# DVD.net
KiCad netlist of a schematic drawn in EAGLE
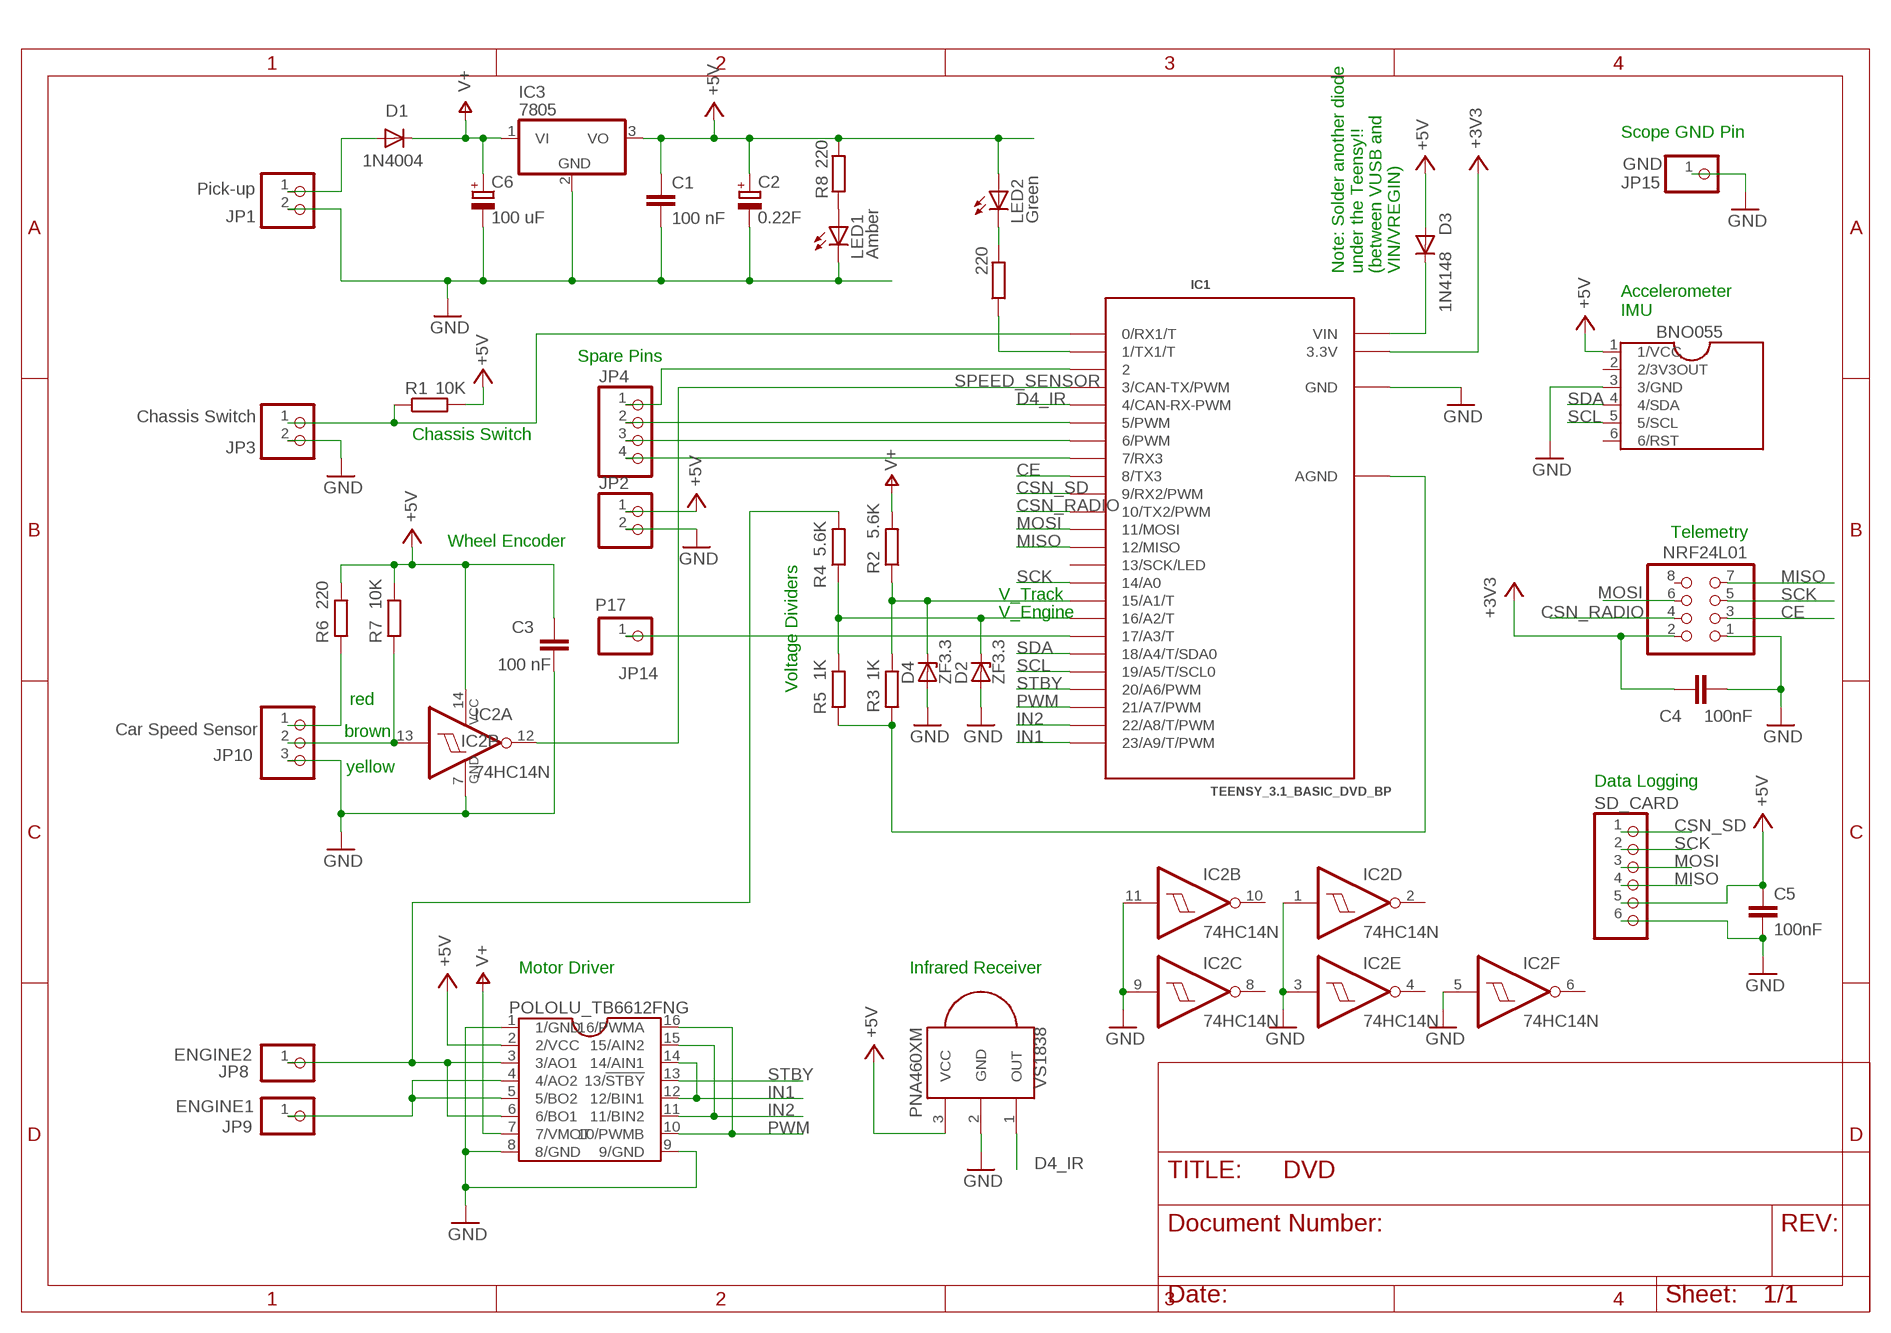
[diagram p0: schematic, sheet 1]

(export (version "E")
  (design (tool "Eeschema 10.0.6"))
  (components
    (comp (ref "BNO055")
      (value "BNO055_LIGHT")
      (footprint "eagle-import:DIL12-6-0")
      (libsource (lib "eagle-import") (part "BNO055_LIGHT"))
    )
    (comp (ref "C1")
      (value "100 nF")
      (footprint "eagle-import:C025-025X050")
      (libsource (lib "eagle-import") (part "resistor_C-EU025-025X050"))
    )
    (comp (ref "C2")
      (value "0.22F")
      (footprint "eagle-import:P128-50")
      (libsource (lib "eagle-import") (part "resistor_CPOL-EUP128-50"))
    )
    (comp (ref "C3")
      (value "100 nF")
      (footprint "eagle-import:C025-025X050")
      (libsource (lib "eagle-import") (part "resistor_C-EU025-025X050"))
    )
    (comp (ref "C4")
      (value "100nF")
      (footprint "eagle-import:C025-025X050")
      (libsource (lib "eagle-import") (part "resistor_C-EU025-025X050"))
    )
    (comp (ref "C5")
      (value "100nF")
      (footprint "eagle-import:C025-024X044")
      (libsource (lib "eagle-import") (part "C-EU025-024X044"))
    )
    (comp (ref "C6")
      (value "100 uF")
      (footprint "eagle-import:E2,5-6")
      (libsource (lib "eagle-import") (part "CPOL-EUE2.5-6"))
    )
    (comp (ref "D1")
      (value "1N4004")
      (footprint "eagle-import:DO41-10")
      (libsource (lib "eagle-import") (part "1N4004"))
    )
    (comp (ref "D2")
      (value "ZF3.3")
      (footprint "eagle-import:ZDIO-7.5")
      (libsource (lib "eagle-import") (part "ZENER-DIODEZD-7.5"))
    )
    (comp (ref "D3")
      (value "1N4148")
      (footprint "eagle-import:DO41-10")
      (libsource (lib "eagle-import") (part "1N4004"))
    )
    (comp (ref "D4")
      (value "ZF3.3")
      (footprint "eagle-import:ZDIO-7.5")
      (libsource (lib "eagle-import") (part "ZENER-DIODEZD-7.5"))
    )
    (comp (ref "IC1")
      (value "TEENSY_3.1_BASIC_DVD_BP")
      (footprint "eagle-import:TEENSY_3.1_BASIC_DVD_BIGPADS")
      (libsource (lib "eagle-import") (part "TEENSY_3.1_BASIC_DVD_BP"))
    )
    (comp (ref "IC2")
      (value "74HC14N")
      (footprint "eagle-import:DIL14")
      (libsource (lib "eagle-import") (part "7414NHC"))
    )
    (comp (ref "IC3")
      (value "7805")
      (footprint "eagle-import:TO220V")
      (libsource (lib "eagle-import") (part "78TV6"))
    )
    (comp (ref "IC4")
      (value "POLOLU_TB6612FNG")
      (footprint "eagle-import:DIL16WIDE")
      (libsource (lib "eagle-import") (part "POLOLU_TB6612FNG"))
    )
    (comp (ref "JP1")
      (value "Pick-up")
      (footprint "eagle-import:1X02")
      (libsource (lib "eagle-import") (part "PINHD-1X2"))
    )
    (comp (ref "JP2")
      (value "PINHD-1X2")
      (footprint "eagle-import:1X02")
      (libsource (lib "eagle-import") (part "PINHD-1X2"))
    )
    (comp (ref "JP3")
      (value "Chassis Switch")
      (footprint "eagle-import:1X02")
      (libsource (lib "eagle-import") (part "PINHD-1X2"))
    )
    (comp (ref "JP4")
      (value "PINHD-1X4")
      (footprint "eagle-import:1X04")
      (libsource (lib "eagle-import") (part "PINHD-1X4"))
    )
    (comp (ref "JP8")
      (value "ENGINE2")
      (footprint "eagle-import:1X01")
      (libsource (lib "eagle-import") (part "PINHD-1X1"))
    )
    (comp (ref "JP9")
      (value "ENGINE1")
      (footprint "eagle-import:1X01")
      (libsource (lib "eagle-import") (part "PINHD-1X1"))
    )
    (comp (ref "JP10")
      (value "Car Speed Sensor")
      (footprint "eagle-import:1X03")
      (libsource (lib "eagle-import") (part "PINHD-1X3"))
    )
    (comp (ref "JP14")
      (value "P17")
      (footprint "eagle-import:1X01")
      (libsource (lib "eagle-import") (part "PINHD-1X1"))
    )
    (comp (ref "JP15")
      (value "GND")
      (footprint "eagle-import:1X01")
      (libsource (lib "eagle-import") (part "PINHD-1X1"))
    )
    (comp (ref "LED1")
      (value "Amber")
      (footprint "eagle-import:LED3MM")
      (libsource (lib "eagle-import") (part "LED3MM"))
    )
    (comp (ref "LED2")
      (value "Green")
      (footprint "eagle-import:LED3MM")
      (libsource (lib "eagle-import") (part "LED3MM"))
    )
    (comp (ref "NRF24L01")
      (value "PINHD-2X4")
      (footprint "eagle-import:2X04")
      (libsource (lib "eagle-import") (part "PINHD-2X4"))
    )
    (comp (ref "R1")
      (value "10K")
      (footprint "eagle-import:0207_10")
      (libsource (lib "eagle-import") (part "R-EU_0207/10"))
    )
    (comp (ref "R2")
      (value "5.6K")
      (footprint "eagle-import:0207_10")
      (libsource (lib "eagle-import") (part "R-EU_0207/10"))
    )
    (comp (ref "R3")
      (value "1K")
      (footprint "eagle-import:0207_10")
      (libsource (lib "eagle-import") (part "R-EU_0207/10"))
    )
    (comp (ref "R4")
      (value "5.6K")
      (footprint "eagle-import:0207_10")
      (libsource (lib "eagle-import") (part "R-EU_0207/10"))
    )
    (comp (ref "R5")
      (value "1K")
      (footprint "eagle-import:0207_10")
      (libsource (lib "eagle-import") (part "R-EU_0207/10"))
    )
    (comp (ref "R6")
      (value "220")
      (footprint "eagle-import:0207_10")
      (libsource (lib "eagle-import") (part "R-EU_0207/10"))
    )
    (comp (ref "R7")
      (value "10K")
      (footprint "eagle-import:0207_10")
      (libsource (lib "eagle-import") (part "R-EU_0207/10"))
    )
    (comp (ref "R8")
      (value "220")
      (footprint "eagle-import:0207_10")
      (libsource (lib "eagle-import") (part "R-EU_0207/10"))
    )
    (comp (ref "R9")
      (value "220")
      (footprint "eagle-import:0207_10")
      (libsource (lib "eagle-import") (part "R-EU_0207/10"))
    )
    (comp (ref "SD_CARD")
      (value "PINHD-1X6")
      (footprint "eagle-import:1X06")
      (libsource (lib "eagle-import") (part "PINHD-1X6"))
    )
    (comp (ref "VS1838")
      (value "PNA460XM")
      (footprint "eagle-import:PNA460XM")
      (libsource (lib "eagle-import") (part "PNA460XM"))
    )
  )
  (nets
    (net (code "1") (name "+3V3") (class "Default")
      (node (ref "C4") (pin "1") (pinfunction "1_1") (pintype "passive"))
      (node (ref "IC1") (pin "3.3V") (pinfunction "3.3V_3.3V") (pintype "power_in"))
      (node (ref "NRF24L01") (pin "2") (pinfunction "2_2") (pintype "passive"))
    )
    (net (code "2") (name "+5V") (class "Default")
      (node (ref "BNO055") (pin "1") (pinfunction "1/VCC_1") (pintype "power_in"))
      (node (ref "C1") (pin "1") (pinfunction "1_1") (pintype "passive"))
      (node (ref "C2") (pin "+") (pinfunction "+_+") (pintype "passive"))
      (node (ref "C3") (pin "1") (pinfunction "1_1") (pintype "passive"))
      (node (ref "C5") (pin "1") (pinfunction "1_1") (pintype "passive"))
      (node (ref "D3") (pin "A") (pinfunction "A_A") (pintype "passive"))
      (node (ref "IC2") (pin "14") (pinfunction "VCC_14") (pintype "power_in"))
      (node (ref "IC3") (pin "3") (pinfunction "VO_3") (pintype "passive"))
      (node (ref "IC4") (pin "2") (pinfunction "2/VCC_2") (pintype "power_in"))
      (node (ref "JP2") (pin "1") (pinfunction "1_1") (pintype "passive"))
      (node (ref "LED2") (pin "A") (pinfunction "A_A") (pintype "passive"))
      (node (ref "R1") (pin "2") (pinfunction "2_2") (pintype "passive"))
      (node (ref "R6") (pin "2") (pinfunction "2_2") (pintype "passive"))
      (node (ref "R7") (pin "2") (pinfunction "2_2") (pintype "passive"))
      (node (ref "R8") (pin "2") (pinfunction "2_2") (pintype "passive"))
      (node (ref "SD_CARD") (pin "5") (pinfunction "5_5") (pintype "passive"))
      (node (ref "VS1838") (pin "3") (pinfunction "VCC_3") (pintype "power_in"))
    )
    (net (code "3") (name "/2{slash}3V3OUT") (class "Default")
      (node (ref "BNO055") (pin "2") (pinfunction "2/3V3OUT_2") (pintype "power_in"))
    )
    (net (code "4") (name "/CE") (class "Default")
      (node (ref "IC1") (pin "8") (pinfunction "8/TX3_8") (pintype "bidirectional"))
      (node (ref "NRF24L01") (pin "3") (pinfunction "3_3") (pintype "passive"))
    )
    (net (code "5") (name "/CSN_RADIO") (class "Default")
      (node (ref "IC1") (pin "10") (pinfunction "10/TX2/PWM_10") (pintype "bidirectional"))
      (node (ref "NRF24L01") (pin "4") (pinfunction "4_4") (pintype "passive"))
    )
    (net (code "6") (name "/CSN_SD") (class "Default")
      (node (ref "IC1") (pin "9") (pinfunction "9/RX2/PWM_9") (pintype "bidirectional"))
      (node (ref "SD_CARD") (pin "1") (pinfunction "1_1") (pintype "passive"))
    )
    (net (code "7") (name "/D4_IR") (class "Default")
      (node (ref "IC1") (pin "4") (pinfunction "4/CAN-RX-PWM_4") (pintype "bidirectional"))
      (node (ref "VS1838") (pin "1") (pinfunction "OUT_1") (pintype "output"))
    )
    (net (code "8") (name "/IN1") (class "Default")
      (node (ref "IC1") (pin "23/A9") (pinfunction "23/A9/T/PWM_23/A9") (pintype "bidirectional"))
      (node (ref "IC4") (pin "12") (pinfunction "12/BIN1_12") (pintype "bidirectional"))
      (node (ref "IC4") (pin "14") (pinfunction "14/AIN1_14") (pintype "bidirectional"))
    )
    (net (code "9") (name "/IN2") (class "Default")
      (node (ref "IC1") (pin "22/A8") (pinfunction "22/A8/T/PWM_22/A8") (pintype "bidirectional"))
      (node (ref "IC4") (pin "11") (pinfunction "11/BIN2_11") (pintype "bidirectional"))
      (node (ref "IC4") (pin "15") (pinfunction "15/AIN2_15") (pintype "bidirectional"))
    )
    (net (code "10") (name "/MISO") (class "Default")
      (node (ref "IC1") (pin "12") (pinfunction "12/MISO_12") (pintype "bidirectional"))
      (node (ref "NRF24L01") (pin "7") (pinfunction "7_7") (pintype "passive"))
      (node (ref "SD_CARD") (pin "4") (pinfunction "4_4") (pintype "passive"))
    )
    (net (code "11") (name "/MOSI") (class "Default")
      (node (ref "IC1") (pin "11") (pinfunction "11/MOSI_11") (pintype "bidirectional"))
      (node (ref "NRF24L01") (pin "6") (pinfunction "6_6") (pintype "passive"))
      (node (ref "SD_CARD") (pin "3") (pinfunction "3_3") (pintype "passive"))
    )
    (net (code "12") (name "/PWM") (class "Default")
      (node (ref "IC1") (pin "21/A7") (pinfunction "21/A7/PWM_21/A7") (pintype "bidirectional"))
      (node (ref "IC4") (pin "10") (pinfunction "10/PWMB_10") (pintype "input"))
      (node (ref "IC4") (pin "16") (pinfunction "16/PWMA_16") (pintype "input"))
    )
    (net (code "13") (name "/SCK") (class "Default")
      (node (ref "IC1") (pin "14/A0") (pinfunction "14/A0_14/A0") (pintype "bidirectional"))
      (node (ref "NRF24L01") (pin "5") (pinfunction "5_5") (pintype "passive"))
      (node (ref "SD_CARD") (pin "2") (pinfunction "2_2") (pintype "passive"))
    )
    (net (code "14") (name "/SCL") (class "Default")
      (node (ref "BNO055") (pin "5") (pinfunction "5/SCL_5") (pintype "bidirectional"))
      (node (ref "IC1") (pin "19/A5") (pinfunction "19/A5/T/SCL0_19/A5") (pintype "bidirectional"))
    )
    (net (code "15") (name "/SDA") (class "Default")
      (node (ref "BNO055") (pin "4") (pinfunction "4/SDA_4") (pintype "bidirectional"))
      (node (ref "IC1") (pin "18/A4") (pinfunction "18/A4/T/SDA0_18/A4") (pintype "bidirectional"))
    )
    (net (code "16") (name "/SPEED_SENSOR") (class "Default")
      (node (ref "IC1") (pin "3") (pinfunction "3/CAN-TX/PWM_3") (pintype "bidirectional"))
      (node (ref "IC2") (pin "12") (pinfunction "O_12") (pintype "output"))
    )
    (net (code "17") (name "/STBY") (class "Default")
      (node (ref "IC1") (pin "20/A6") (pinfunction "20/A6/PWM_20/A6") (pintype "bidirectional"))
      (node (ref "IC4") (pin "13") (pinfunction "13/~{STBY}_13") (pintype "input"))
    )
    (net (code "18") (name "GND") (class "Default")
      (node (ref "BNO055") (pin "3") (pinfunction "3/GND_3") (pintype "power_in"))
      (node (ref "C1") (pin "2") (pinfunction "2_2") (pintype "passive"))
      (node (ref "C2") (pin "-") (pinfunction "-_-") (pintype "passive"))
      (node (ref "C3") (pin "2") (pinfunction "2_2") (pintype "passive"))
      (node (ref "C4") (pin "2") (pinfunction "2_2") (pintype "passive"))
      (node (ref "C5") (pin "2") (pinfunction "2_2") (pintype "passive"))
      (node (ref "C6") (pin "-") (pinfunction "-_-") (pintype "passive"))
      (node (ref "D2") (pin "A") (pinfunction "A_A") (pintype "passive"))
      (node (ref "D4") (pin "A") (pinfunction "A_A") (pintype "passive"))
      (node (ref "IC1") (pin "GND") (pinfunction "GND_GND") (pintype "power_in"))
      (node (ref "IC2") (pin "1") (pinfunction "I_1") (pintype "input"))
      (node (ref "IC2") (pin "11") (pinfunction "I_11") (pintype "input"))
      (node (ref "IC2") (pin "3") (pinfunction "I_3") (pintype "input"))
      (node (ref "IC2") (pin "5") (pinfunction "I_5") (pintype "input"))
      (node (ref "IC2") (pin "7") (pinfunction "GND_7") (pintype "power_in"))
      (node (ref "IC2") (pin "9") (pinfunction "I_9") (pintype "input"))
      (node (ref "IC3") (pin "2") (pinfunction "GND_2") (pintype "passive"))
      (node (ref "IC4") (pin "1") (pinfunction "1/GND_1") (pintype "power_in"))
      (node (ref "IC4") (pin "8") (pinfunction "8/GND_8") (pintype "power_in"))
      (node (ref "IC4") (pin "9") (pinfunction "9/GND_9") (pintype "power_in"))
      (node (ref "JP1") (pin "2") (pinfunction "2_2") (pintype "passive"))
      (node (ref "JP10") (pin "3") (pinfunction "3_3") (pintype "passive"))
      (node (ref "JP15") (pin "1") (pinfunction "1_1") (pintype "passive"))
      (node (ref "JP2") (pin "2") (pinfunction "2_2") (pintype "passive"))
      (node (ref "JP3") (pin "2") (pinfunction "2_2") (pintype "passive"))
      (node (ref "LED1") (pin "K") (pinfunction "C_K") (pintype "passive"))
      (node (ref "NRF24L01") (pin "1") (pinfunction "1_1") (pintype "passive"))
      (node (ref "SD_CARD") (pin "6") (pinfunction "6_6") (pintype "passive"))
      (node (ref "VS1838") (pin "2") (pinfunction "GND_2") (pintype "power_in"))
    )
    (net (code "19") (name "Net-(D1-PadA)") (class "Default")
      (node (ref "D1") (pin "A") (pinfunction "A_A") (pintype "passive"))
      (node (ref "JP1") (pin "1") (pinfunction "1_1") (pintype "passive"))
    )
    (net (code "20") (name "Net-(D3-PadC)") (class "Default")
      (node (ref "D3") (pin "C") (pinfunction "C_C") (pintype "passive"))
      (node (ref "IC1") (pin "VIN") (pinfunction "VIN_VIN") (pintype "power_in"))
    )
    (net (code "21") (name "Net-(IC1-0{slash}RX1{slash}T)") (class "Default")
      (node (ref "IC1") (pin "0") (pinfunction "0/RX1/T_0") (pintype "bidirectional"))
      (node (ref "JP3") (pin "1") (pinfunction "1_1") (pintype "passive"))
      (node (ref "R1") (pin "1") (pinfunction "1_1") (pintype "passive"))
    )
    (net (code "22") (name "Net-(IC1-1{slash}TX1{slash}T)") (class "Default")
      (node (ref "IC1") (pin "1") (pinfunction "1/TX1/T_1") (pintype "bidirectional"))
      (node (ref "R9") (pin "1") (pinfunction "1_1") (pintype "passive"))
    )
    (net (code "23") (name "Net-(IC1-5{slash}PWM)") (class "Default")
      (node (ref "IC1") (pin "5") (pinfunction "5/PWM_5") (pintype "bidirectional"))
      (node (ref "JP4") (pin "2") (pinfunction "2_2") (pintype "passive"))
    )
    (net (code "24") (name "Net-(IC1-6{slash}PWM)") (class "Default")
      (node (ref "IC1") (pin "6") (pinfunction "6/PWM_6") (pintype "bidirectional"))
      (node (ref "JP4") (pin "3") (pinfunction "3_3") (pintype "passive"))
    )
    (net (code "25") (name "Net-(IC1-7{slash}RX3)") (class "Default")
      (node (ref "IC1") (pin "7") (pinfunction "7/RX3_7") (pintype "bidirectional"))
      (node (ref "JP4") (pin "4") (pinfunction "4_4") (pintype "passive"))
    )
    (net (code "26") (name "Net-(IC1-15{slash}A1{slash}T)") (class "Default")
      (node (ref "D4") (pin "C") (pinfunction "C_C") (pintype "passive"))
      (node (ref "IC1") (pin "15/A1") (pinfunction "15/A1/T_15/A1") (pintype "bidirectional"))
      (node (ref "R2") (pin "1") (pinfunction "1_1") (pintype "passive"))
      (node (ref "R3") (pin "2") (pinfunction "2_2") (pintype "passive"))
    )
    (net (code "27") (name "Net-(IC1-16{slash}A2{slash}T)") (class "Default")
      (node (ref "D2") (pin "C") (pinfunction "C_C") (pintype "passive"))
      (node (ref "IC1") (pin "16/A2") (pinfunction "16/A2/T_16/A2") (pintype "bidirectional"))
      (node (ref "R4") (pin "1") (pinfunction "1_1") (pintype "passive"))
      (node (ref "R5") (pin "2") (pinfunction "2_2") (pintype "passive"))
    )
    (net (code "28") (name "Net-(IC1-17{slash}A3{slash}T)") (class "Default")
      (node (ref "IC1") (pin "17/A3") (pinfunction "17/A3/T_17/A3") (pintype "bidirectional"))
      (node (ref "JP14") (pin "1") (pinfunction "1_1") (pintype "passive"))
    )
    (net (code "29") (name "Net-(IC1-Pad2)") (class "Default")
      (node (ref "IC1") (pin "2") (pinfunction "2_2") (pintype "bidirectional"))
      (node (ref "JP4") (pin "1") (pinfunction "1_1") (pintype "passive"))
    )
    (net (code "30") (name "Net-(IC1-PadAGND)") (class "Default")
      (node (ref "IC1") (pin "AGND") (pinfunction "AGND_AGND") (pintype "power_in"))
      (node (ref "R3") (pin "1") (pinfunction "1_1") (pintype "passive"))
      (node (ref "R5") (pin "1") (pinfunction "1_1") (pintype "passive"))
    )
    (net (code "31") (name "Net-(IC2A-I)") (class "Default")
      (node (ref "IC2") (pin "13") (pinfunction "I_13") (pintype "input"))
      (node (ref "JP10") (pin "2") (pinfunction "2_2") (pintype "passive"))
      (node (ref "R7") (pin "1") (pinfunction "1_1") (pintype "passive"))
    )
    (net (code "32") (name "Net-(IC4-3{slash}AO1)") (class "Default")
      (node (ref "IC4") (pin "3") (pinfunction "3/AO1_3") (pintype "bidirectional"))
      (node (ref "IC4") (pin "6") (pinfunction "6/BO1_6") (pintype "bidirectional"))
      (node (ref "JP8") (pin "1") (pinfunction "1_1") (pintype "passive"))
      (node (ref "R4") (pin "2") (pinfunction "2_2") (pintype "passive"))
    )
    (net (code "33") (name "Net-(IC4-4{slash}AO2)") (class "Default")
      (node (ref "IC4") (pin "4") (pinfunction "4/AO2_4") (pintype "bidirectional"))
      (node (ref "IC4") (pin "5") (pinfunction "5/BO2_5") (pintype "bidirectional"))
      (node (ref "JP9") (pin "1") (pinfunction "1_1") (pintype "passive"))
    )
    (net (code "34") (name "Net-(JP10-Pad1)") (class "Default")
      (node (ref "JP10") (pin "1") (pinfunction "1_1") (pintype "passive"))
      (node (ref "R6") (pin "1") (pinfunction "1_1") (pintype "passive"))
    )
    (net (code "35") (name "Net-(LED1-PadA)") (class "Default")
      (node (ref "LED1") (pin "A") (pinfunction "A_A") (pintype "passive"))
      (node (ref "R8") (pin "1") (pinfunction "1_1") (pintype "passive"))
    )
    (net (code "36") (name "Net-(LED2-C)") (class "Default")
      (node (ref "LED2") (pin "K") (pinfunction "C_K") (pintype "passive"))
      (node (ref "R9") (pin "2") (pinfunction "2_2") (pintype "passive"))
    )
    (net (code "37") (name "V+") (class "Default")
      (node (ref "C6") (pin "+") (pinfunction "+_+") (pintype "passive"))
      (node (ref "D1") (pin "C") (pinfunction "C_C") (pintype "passive"))
      (node (ref "IC3") (pin "1") (pinfunction "VI_1") (pintype "input"))
      (node (ref "IC4") (pin "7") (pinfunction "7/VMOT_7") (pintype "power_in"))
      (node (ref "R2") (pin "2") (pinfunction "2_2") (pintype "passive"))
    )
    (net (code "38") (name "unconnected-(BNO055-6{slash}RST-Pad6)") (class "Default")
      (node (ref "BNO055") (pin "6") (pinfunction "6/RST_6") (pintype "input"))
    )
    (net (code "39") (name "unconnected-(IC1-13{slash}SCK{slash}LED-Pad13)") (class "Default")
      (node (ref "IC1") (pin "13") (pinfunction "13/SCK/LED_13") (pintype "bidirectional"))
    )
    (net (code "40") (name "unconnected-(IC2B-O-Pad10)") (class "Default")
      (node (ref "IC2") (pin "10") (pinfunction "O_10") (pintype "output"))
    )
    (net (code "41") (name "unconnected-(IC2C-O-Pad8)") (class "Default")
      (node (ref "IC2") (pin "8") (pinfunction "O_8") (pintype "output"))
    )
    (net (code "42") (name "unconnected-(IC2D-O-Pad2)") (class "Default")
      (node (ref "IC2") (pin "2") (pinfunction "O_2") (pintype "output"))
    )
    (net (code "43") (name "unconnected-(IC2E-O-Pad4)") (class "Default")
      (node (ref "IC2") (pin "4") (pinfunction "O_4") (pintype "output"))
    )
    (net (code "44") (name "unconnected-(IC2F-O-Pad6)") (class "Default")
      (node (ref "IC2") (pin "6") (pinfunction "O_6") (pintype "output"))
    )
    (net (code "45") (name "unconnected-(NRF24L01-Pad8)") (class "Default")
      (node (ref "NRF24L01") (pin "8") (pinfunction "8_8") (pintype "passive"))
    )
  )
)
